# lipo_battery.net
KiCad netlist of a schematic drawn in Altium Designer
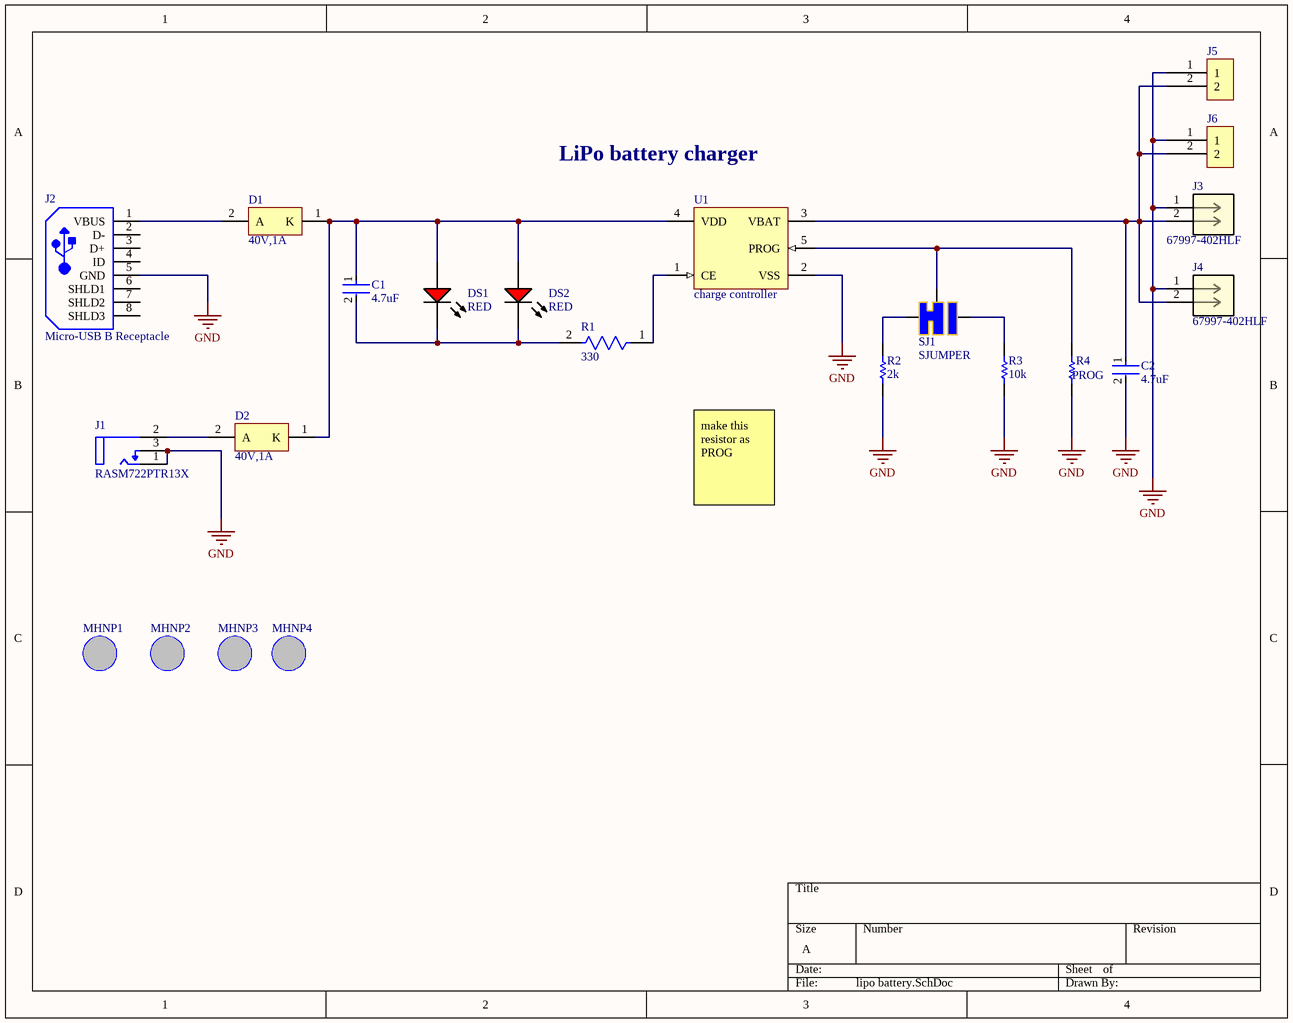
[diagram p0: lipo battery.SchDoc]

(export (version "E")
  (design (tool "Eeschema 10.0.6"))
  (components
    (comp (ref "C1")
      (value "4.7uF")
      (footprint "FP-CC0603-DA-MFG")
      (description "CAP CER 4.7UF 6.3V X5R 0603")
      (fields (field (name "TOLERANCE") "0.1") (field (name "MANUFACTURER PART NUMBER") "CC0603KRX5R5BB475"))
      (libsource (lib "Altium Content Vault") (part "11868f565c42a9108669ba33697ecf6"))
    )
    (comp (ref "C2")
      (value "4.7uF")
      (footprint "FP-CC0603-DA-MFG")
      (description "CAP CER 4.7UF 6.3V X5R 0603")
      (fields (field (name "TOLERANCE") "0.1") (field (name "MANUFACTURER PART NUMBER") "CC0603KRX5R5BB475"))
      (libsource (lib "Altium Content Vault") (part "11868f565c42a9108669ba33697ecf6"))
    )
    (comp (ref "D1")
      (value "40V,1A")
      (footprint "ONSC-SMA-2-403D-02_V")
      (description "Schottky Power Rectifier, 2-Pin SMA, Pb-Free, Tape and Reel")
      (fields (field (name "PARTNUMBER") "MBRA140T3G") (field (name "MANUFACTURER") "On Semiconductor"))
      (libsource (lib "Altium Content Vault") (part "ONSC-D-K1A2-2_A"))
    )
    (comp (ref "D2")
      (value "40V,1A")
      (footprint "ONSC-SMA-2-403D-02_V")
      (description "Schottky Power Rectifier, 2-Pin SMA, Pb-Free, Tape and Reel")
      (fields (field (name "PARTNUMBER") "MBRA140T3G") (field (name "MANUFACTURER") "On Semiconductor"))
      (libsource (lib "Altium Content Vault") (part "ONSC-D-K1A2-2_A"))
    )
    (comp (ref "DS1")
      (value "RED")
      (footprint "VISH-TLMS1000_V")
      (description "Low Current LED, 40 mW, 1.8 V, -40 to 100 degC, 2-Pin SMD (0603), RoHS, Tape and Reel")
      (fields (field (name "MANUFACTURER") "Vishay"))
      (libsource (lib "Altium Content Vault") (part "LED-RED-AK-2"))
    )
    (comp (ref "DS2")
      (value "RED")
      (footprint "VISH-TLMS1000_V")
      (description "Low Current LED, 40 mW, 1.8 V, -40 to 100 degC, 2-Pin SMD (0603), RoHS, Tape and Reel")
      (fields (field (name "MANUFACTURER") "Vishay"))
      (libsource (lib "Altium Content Vault") (part "LED-RED-AK-2"))
    )
    (comp (ref "J1")
      (value "RASM722PTR13X")
      (footprint "FP-RASM722PTR13X-MFG")
      (description "CONN PWR JACK 2.1X5.5MM SOLDER")
      (libsource (lib "Altium Content Vault") (part "69023cd999ddc70d2a190894d9bbb58"))
    )
    (comp (ref "J2")
      (value "Micro-USB B Receptacle")
      (footprint "MOLX-105133-0001_V")
      (description "Micro-USB B Receptacle, Vertical, -30 to 85 degC, 5-Pin SMD, RoHS, Tape and Reel")
      (fields (field (name "MANUFACTURER") "Molex") (field (name "PARTNUMBER") "105133-0001"))
      (libsource (lib "Altium Content Vault") (part "USB-5-3SHLD"))
    )
    (comp (ref "J3")
      (value "67997-402HLF")
      (footprint "2Pins_AMP")
      (description "No Description Available")
      (libsource (lib "67997-402HLF") (part "67997-402HLF"))
    )
    (comp (ref "J4")
      (value "67997-402HLF")
      (footprint "2Pins_AMP")
      (description "No Description Available")
      (libsource (lib "67997-402HLF") (part "67997-402HLF"))
    )
    (comp (ref "J5")
      (value "CONN HEADER R/A 2POS 5.08MM")
      (footprint "1-179276-2")
      (fields
        (field (name "MANUFACTURER") "TE Connectivity AMP Connectors")
        (field (name "MANUFACTURER PART NUMBER") "1-179276-2")
      )
      (libsource (lib "lipo battery") (part "1-179276-2"))
    )
    (comp (ref "J6")
      (value "CONN HEADER R/A 2POS 5.08MM")
      (footprint "1-179276-2")
      (fields
        (field (name "MANUFACTURER") "TE Connectivity AMP Connectors")
        (field (name "MANUFACTURER PART NUMBER") "1-179276-2")
      )
      (libsource (lib "lipo battery") (part "1-179276-2"))
    )
    (comp (ref "MHNP1")
      (value "MOUNTING HOLE NON PLATED 3.2MM")
      (footprint "MPHNP3P2MM")
      (description "MOUNTING HOLE NON PLATED 3.2MM DRILL HOLE")
      (libsource (lib "CRICLE") (part "MTH3P2MM"))
    )
    (comp (ref "MHNP2")
      (value "MOUNTING HOLE NON PLATED 3.2MM")
      (footprint "MPHNP3P2MM")
      (description "MOUNTING HOLE NON PLATED 3.2MM DRILL HOLE")
      (libsource (lib "CRICLE") (part "MTH3P2MM"))
    )
    (comp (ref "MHNP3")
      (value "MOUNTING HOLE NON PLATED 3.2MM")
      (footprint "MPHNP3P2MM")
      (description "MOUNTING HOLE NON PLATED 3.2MM DRILL HOLE")
      (libsource (lib "CRICLE") (part "MTH3P2MM"))
    )
    (comp (ref "MHNP4")
      (value "MOUNTING HOLE NON PLATED 3.2MM")
      (footprint "MPHNP3P2MM")
      (description "MOUNTING HOLE NON PLATED 3.2MM DRILL HOLE")
      (libsource (lib "CRICLE") (part "MTH3P2MM"))
    )
    (comp (ref "R1")
      (value "330")
      (footprint "FP-CRCW0805-e3-MFG")
      (description "RES Thick Film, 330Ω, 1%, 0.125W, 100ppm/°C, 0805")
      (fields (field (name "TOLERANCE") "1%"))
      (libsource (lib "Altium Content Vault") (part "1029c3af85768c4190bb7ad29bc67b5"))
    )
    (comp (ref "R2")
      (value "2k")
      (footprint "RESC2013X70X40LL20T20")
      (fields (field (name "PART NUMBER") "ERJ-6GEYJ202V") (field (name "MANUFACTURER") "Panasonic"))
      (libsource (lib "Altium Content Vault") (part "RES"))
    )
    (comp (ref "R3")
      (value "10k")
      (footprint "RESC2013X70X40ML20T20")
      (fields (field (name "MANUFACTURER") "Panasonic") (field (name "PART NUMBER") "ERJ-6ENF1002V"))
      (libsource (lib "Altium Content Vault") (part "RES"))
    )
    (comp (ref "R4")
      (value "PROG")
      (footprint "VISH-A1-2_V2")
      (description "Power Metal Film Leaded Resistor, 62 KOhm +/-5%, 2 W, 2-Pin THD, RoHS, Ammo Pack")
      (fields (field (name "TOLERANCE") "+/-5%") (field (name "POWER") "2 W"))
      (libsource (lib "Altium Content Vault") (part "VISH-RES-2"))
    )
    (comp (ref "SJ1")
      (value "SJUMPER")
      (footprint "SJUMPER")
      (description "solder jumper 3 pads and pins")
      (libsource (lib "SJUMPER") (part "SJUMPER"))
    )
    (comp (ref "U1")
      (value "charge controller")
      (footprint "SOT-23-OT5_M")
      (libsource (lib "Altium Content Vault") (part "PM-BM-MCP7381X-SOT5"))
    )
  )
  (nets
    (net (code "1") (name "GND") (class "Default")
      (node (ref "C2") (pin "2") (pinfunction "2_2") (pintype "passive"))
      (node (ref "J1") (pin "1") (pinfunction "TIP_TERMINAL(CENTER_PIN)_1") (pintype "passive"))
      (node (ref "J1") (pin "3") (pinfunction "SHUNT_TERMINAL_3") (pintype "passive"))
      (node (ref "J2") (pin "5") (pinfunction "GND_5") (pintype "passive"))
      (node (ref "J3") (pin "1") (pinfunction "1_1") (pintype "passive"))
      (node (ref "J4") (pin "1") (pinfunction "1_1") (pintype "passive"))
      (node (ref "J5") (pin "1") (pinfunction "1_1") (pintype "passive"))
      (node (ref "J6") (pin "1") (pinfunction "1_1") (pintype "passive"))
      (node (ref "R2") (pin "1") (pinfunction "1_1") (pintype "passive"))
      (node (ref "R3") (pin "1") (pinfunction "1_1") (pintype "passive"))
      (node (ref "R4") (pin "1") (pinfunction "1_1") (pintype "passive"))
      (node (ref "U1") (pin "2") (pinfunction "VSS_2") (pintype "power_in"))
    )
    (net (code "2") (name "Net-(D1-A)") (class "Default")
      (node (ref "D1") (pin "2") (pinfunction "A_2") (pintype "passive"))
      (node (ref "J2") (pin "1") (pinfunction "VBUS_1") (pintype "passive"))
    )
    (net (code "3") (name "Net-(D1-K)") (class "Default")
      (node (ref "C1") (pin "1") (pinfunction "1_1") (pintype "passive"))
      (node (ref "D1") (pin "1") (pinfunction "K_1") (pintype "passive"))
      (node (ref "D2") (pin "1") (pinfunction "K_1") (pintype "passive"))
      (node (ref "DS1") (pin "1") (pinfunction "A_1") (pintype "passive"))
      (node (ref "DS2") (pin "1") (pinfunction "A_1") (pintype "passive"))
      (node (ref "U1") (pin "4") (pinfunction "VDD_4") (pintype "power_in"))
    )
    (net (code "4") (name "Net-(D2-A)") (class "Default")
      (node (ref "D2") (pin "2") (pinfunction "A_2") (pintype "passive"))
      (node (ref "J1") (pin "2") (pinfunction "SLEEVE_TERMINAL_2") (pintype "passive"))
    )
    (net (code "5") (name "Net-(DS1-K)") (class "Default")
      (node (ref "C1") (pin "2") (pinfunction "2_2") (pintype "passive"))
      (node (ref "DS1") (pin "2") (pinfunction "K_2") (pintype "passive"))
      (node (ref "DS2") (pin "2") (pinfunction "K_2") (pintype "passive"))
      (node (ref "R1") (pin "2") (pinfunction "2_2") (pintype "passive"))
    )
    (net (code "6") (name "Net-(R2-Pad2)") (class "Default")
      (node (ref "R2") (pin "2") (pinfunction "2_2") (pintype "passive"))
      (node (ref "SJ1") (pin "1") (pinfunction "1_1") (pintype "passive"))
    )
    (net (code "7") (name "Net-(R3-Pad2)") (class "Default")
      (node (ref "R3") (pin "2") (pinfunction "2_2") (pintype "passive"))
      (node (ref "SJ1") (pin "3") (pinfunction "3_3") (pintype "passive"))
    )
    (net (code "8") (name "Net-(U1-CE)") (class "Default")
      (node (ref "R1") (pin "1") (pinfunction "1_1") (pintype "passive"))
      (node (ref "U1") (pin "1") (pinfunction "CE_1") (pintype "input"))
    )
    (net (code "9") (name "Net-(U1-PROG)") (class "Default")
      (node (ref "R4") (pin "2") (pinfunction "2_2") (pintype "passive"))
      (node (ref "SJ1") (pin "2") (pinfunction "2_2") (pintype "passive"))
      (node (ref "U1") (pin "5") (pinfunction "PROG_5") (pintype "input"))
    )
    (net (code "10") (name "Net-(U1-VBAT)") (class "Default")
      (node (ref "C2") (pin "1") (pinfunction "1_1") (pintype "passive"))
      (node (ref "J3") (pin "2") (pinfunction "2_2") (pintype "passive"))
      (node (ref "J4") (pin "2") (pinfunction "2_2") (pintype "passive"))
      (node (ref "J5") (pin "2") (pinfunction "2_2") (pintype "passive"))
      (node (ref "J6") (pin "2") (pinfunction "2_2") (pintype "passive"))
      (node (ref "U1") (pin "3") (pinfunction "VBAT_3") (pintype "power_in"))
    )
    (net (code "11") (name "unconnected-(J2-D+-Pad3)") (class "Default")
      (node (ref "J2") (pin "3") (pinfunction "D+_3") (pintype "passive"))
    )
    (net (code "12") (name "unconnected-(J2-D--Pad2)") (class "Default")
      (node (ref "J2") (pin "2") (pinfunction "D-_2") (pintype "passive"))
    )
    (net (code "13") (name "unconnected-(J2-ID-Pad4)") (class "Default")
      (node (ref "J2") (pin "4") (pinfunction "ID_4") (pintype "passive"))
    )
    (net (code "14") (name "unconnected-(J2-SHLD1-Pad6)") (class "Default")
      (node (ref "J2") (pin "6") (pinfunction "SHLD1_6") (pintype "passive"))
    )
    (net (code "15") (name "unconnected-(J2-SHLD2-Pad7)") (class "Default")
      (node (ref "J2") (pin "7") (pinfunction "SHLD2_7") (pintype "passive"))
    )
    (net (code "16") (name "unconnected-(J2-SHLD3-Pad8)") (class "Default")
      (node (ref "J2") (pin "8") (pinfunction "SHLD3_8") (pintype "passive"))
    )
  )
)
